# multicharger-redux.net
KiCad netlist of a schematic drawn in EAGLE
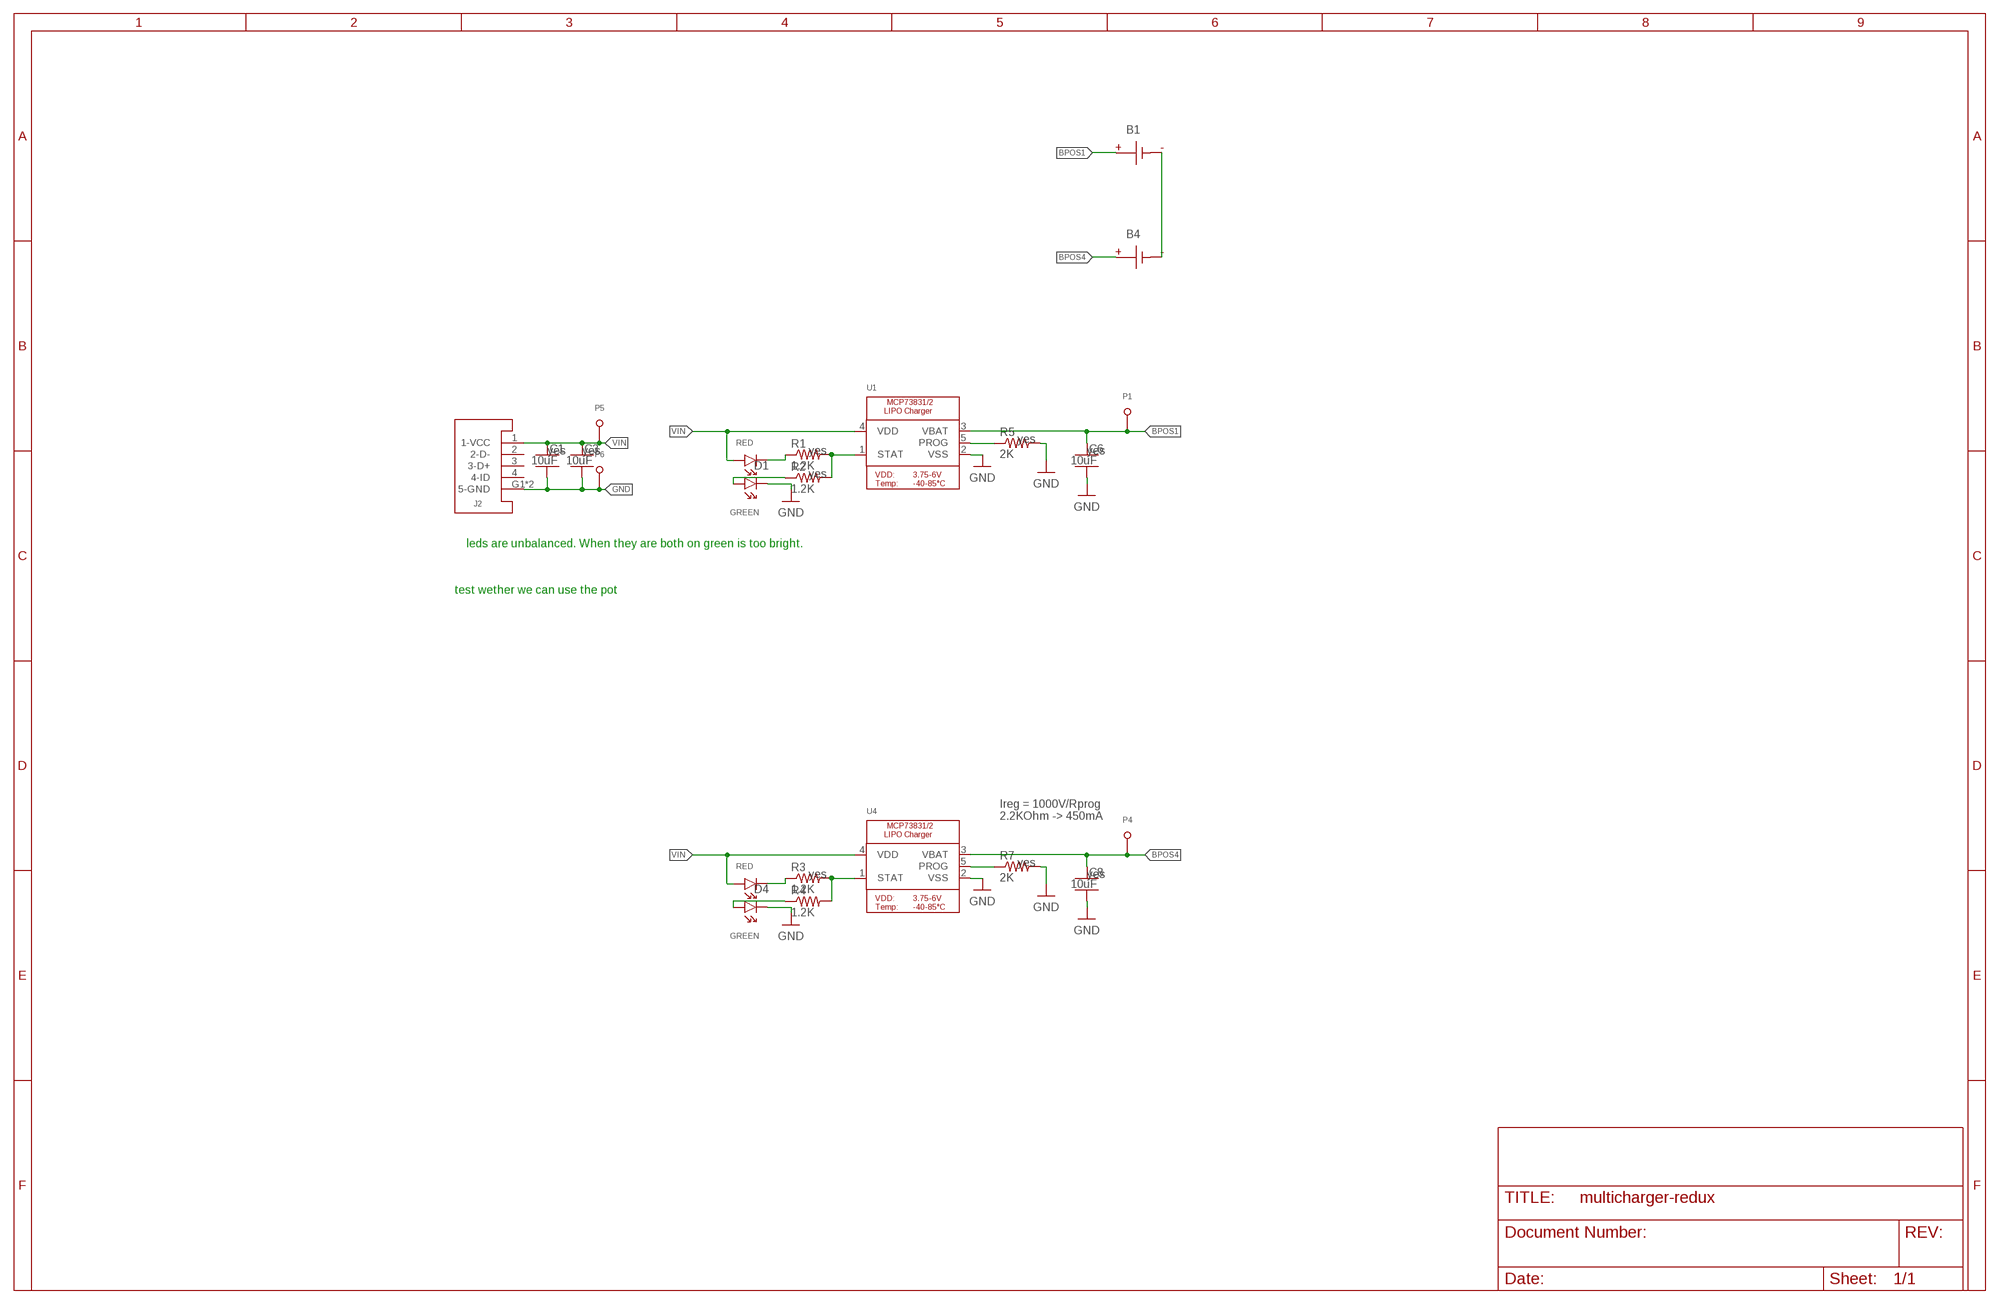
[diagram p0: schematic, sheet 1]

(export (version "E")
  (design (tool "Eeschema 10.0.6"))
  (components
    (comp (ref "B1")
      (value "BATTERY-SMD")
      (footprint "eagle-import:MOLEX-BATTERY-CONNECTOR-SMD-51005-2P")
      (fields (field (name "MFR") "UNKNOWN") (field (name "CREATOR") "Swanson"))
      (libsource (lib "eagle-import") (part "BATTERY-SMD"))
    )
    (comp (ref "B4")
      (value "BATTERY-SMD")
      (footprint "eagle-import:MOLEX-BATTERY-CONNECTOR-SMD-51005-2P")
      (fields (field (name "MFR") "UNKNOWN") (field (name "CREATOR") "Swanson"))
      (libsource (lib "eagle-import") (part "BATTERY-SMD"))
    )
    (comp (ref "C1")
      (value "10uF")
      (footprint "eagle-import:CAPC2012X140_HS")
      (fields
        (field (name "MFR") "TDK")
        (field (name "MPN") "C2012X5R1E106K125AB")
        (field (name "SUBSTITUTE_OK") "yes")
        (field (name "CREATOR") "Swanson")
        (field (name "REVIEWER") "Swanson")
      )
      (libsource (lib "eagle-import") (part "CAPACITOR-NP_SMD-2012-0805_CERAMIC-10UF"))
    )
    (comp (ref "C3")
      (value "10uF")
      (footprint "eagle-import:CAPC2012X140_HS")
      (fields
        (field (name "MFR") "TDK")
        (field (name "MPN") "C2012X5R1E106K125AB")
        (field (name "SUBSTITUTE_OK") "yes")
        (field (name "CREATOR") "Swanson")
        (field (name "REVIEWER") "Swanson")
      )
      (libsource (lib "eagle-import") (part "CAPACITOR-NP_SMD-2012-0805_CERAMIC-10UF"))
    )
    (comp (ref "C6")
      (value "10uF")
      (footprint "eagle-import:CAPC2012X140_HS")
      (fields
        (field (name "MFR") "TDK")
        (field (name "MPN") "C2012X5R1E106K125AB")
        (field (name "SUBSTITUTE_OK") "yes")
        (field (name "CREATOR") "Swanson")
        (field (name "REVIEWER") "Swanson")
      )
      (libsource (lib "eagle-import") (part "CAPACITOR-NP_SMD-2012-0805_CERAMIC-10UF"))
    )
    (comp (ref "C8")
      (value "10uF")
      (footprint "eagle-import:CAPC2012X140_HS")
      (fields
        (field (name "MFR") "TDK")
        (field (name "MPN") "C2012X5R1E106K125AB")
        (field (name "SUBSTITUTE_OK") "yes")
        (field (name "CREATOR") "Swanson")
        (field (name "REVIEWER") "Swanson")
      )
      (libsource (lib "eagle-import") (part "CAPACITOR-NP_SMD-2012-0805_CERAMIC-10UF"))
    )
    (comp (ref "D1")
      (value "LED-2X-GREEN/RED-1.6X1.5MM")
      (footprint "eagle-import:LED-2X-LITE-ON-1.6MMX1.5MM")
      (fields
        (field (name "COLOR2") "GREEN")
        (field (name "COLOR1") "RED")
        (field (name "MFR") "Lite-On Inc.")
        (field (name "MPN") "LTST-C195TGKRKT")
        (field (name "CREATOR") "Swanson")
      )
      (libsource (lib "eagle-import") (part "LED-2X-GREEN/RED-1.6X1.5MM"))
    )
    (comp (ref "D4")
      (value "LED-2X-GREEN/RED-1.6X1.5MM")
      (footprint "eagle-import:LED-2X-LITE-ON-1.6MMX1.5MM")
      (fields
        (field (name "COLOR2") "GREEN")
        (field (name "COLOR1") "RED")
        (field (name "MFR") "Lite-On Inc.")
        (field (name "MPN") "LTST-C195TGKRKT")
        (field (name "CREATOR") "Swanson")
      )
      (libsource (lib "eagle-import") (part "LED-2X-GREEN/RED-1.6X1.5MM"))
    )
    (comp (ref "J2")
      (value "USB-A-SMD-KEYSTONE-931")
      (footprint "eagle-import:USB-A-KEYSTONE-931")
      (fields
        (field (name "MFR") "Keystone Electronics")
        (field (name "MPN") "931")
        (field (name "CREATOR") "Swanson")
      )
      (libsource (lib "eagle-import") (part "USB-A-SMD-KEYSTONE-931"))
    )
    (comp (ref "P1")
      (value "TEST-POINT-1MM")
      (footprint "eagle-import:TEST-POINT-1MM-VIA")
      (fields (field (name "CREATOR") "Swanson"))
      (libsource (lib "eagle-import") (part "TEST-POINT-1MM"))
    )
    (comp (ref "P4")
      (value "TEST-POINT-1MM")
      (footprint "eagle-import:TEST-POINT-1MM-VIA")
      (fields (field (name "CREATOR") "Swanson"))
      (libsource (lib "eagle-import") (part "TEST-POINT-1MM"))
    )
    (comp (ref "P5")
      (value "TEST-POINT-1MM")
      (footprint "eagle-import:TEST-POINT-1MM-VIA")
      (fields (field (name "CREATOR") "Swanson"))
      (libsource (lib "eagle-import") (part "TEST-POINT-1MM"))
    )
    (comp (ref "P6")
      (value "TEST-POINT-1MM")
      (footprint "eagle-import:TEST-POINT-1MM-VIA")
      (fields (field (name "CREATOR") "Swanson"))
      (libsource (lib "eagle-import") (part "TEST-POINT-1MM"))
    )
    (comp (ref "R1")
      (value "1.2K")
      (footprint "eagle-import:RESC2012X60_HS")
      (fields
        (field (name "MFR") "Yageo")
        (field (name "MPN") "RC0805FR-071K2L")
        (field (name "SUBSTITUTE_OK") "yes")
        (field (name "CREATOR") "Swanson")
      )
      (libsource (lib "eagle-import") (part "RESISTOR_SMD-2012-0805-1.2K"))
    )
    (comp (ref "R2")
      (value "1.2K")
      (footprint "eagle-import:RESC2012X60_HS")
      (fields
        (field (name "MFR") "Yageo")
        (field (name "MPN") "RC0805FR-071K2L")
        (field (name "SUBSTITUTE_OK") "yes")
        (field (name "CREATOR") "Swanson")
      )
      (libsource (lib "eagle-import") (part "RESISTOR_SMD-2012-0805-1.2K"))
    )
    (comp (ref "R3")
      (value "1.2K")
      (footprint "eagle-import:RESC2012X60_HS")
      (fields
        (field (name "MFR") "Yageo")
        (field (name "MPN") "RC0805FR-071K2L")
        (field (name "SUBSTITUTE_OK") "yes")
        (field (name "CREATOR") "Swanson")
      )
      (libsource (lib "eagle-import") (part "RESISTOR_SMD-2012-0805-1.2K"))
    )
    (comp (ref "R4")
      (value "1.2K")
      (footprint "eagle-import:RESC2012X60_HS")
      (fields
        (field (name "MFR") "Yageo")
        (field (name "MPN") "RC0805FR-071K2L")
        (field (name "CREATOR") "Swanson")
      )
      (libsource (lib "eagle-import") (part "RESISTOR_SMD-2012-0805-1.2K"))
    )
    (comp (ref "R5")
      (value "2K")
      (footprint "eagle-import:RESC2012X60_HS")
      (fields
        (field (name "MFR") "YAGEO")
        (field (name "MPN") "AC0805FR-071K2L")
        (field (name "SUBSTITUTE_OK") "yes")
        (field (name "CREATOR") "Swanson")
      )
      (libsource (lib "eagle-import") (part "RESISTOR_SMD-2012-0805-2K"))
    )
    (comp (ref "R7")
      (value "2K")
      (footprint "eagle-import:RESC2012X60_HS")
      (fields
        (field (name "MFR") "YAGEO")
        (field (name "MPN") "AC0805FR-071K2L")
        (field (name "SUBSTITUTE_OK") "yes")
        (field (name "CREATOR") "Swanson")
      )
      (libsource (lib "eagle-import") (part "RESISTOR_SMD-2012-0805-2K"))
    )
    (comp (ref "U1")
      (value "MCP73831T-2ACI/OT")
      (footprint "eagle-import:SOT23-5")
      (fields (field (name "MFR") "Microchip Technology") (field (name "CREATOR") "Adafruit"))
      (libsource (lib "eagle-import") (part "MCP73831/2"))
    )
    (comp (ref "U4")
      (value "MCP73831T-2ACI/OT")
      (footprint "eagle-import:SOT23-5")
      (fields (field (name "MFR") "Microchip Technology") (field (name "CREATOR") "Adafruit"))
      (libsource (lib "eagle-import") (part "MCP73831/2"))
    )
  )
  (nets
    (net (code "1") (name "BPOS1") (class "Default")
      (node (ref "B1") (pin "P") (pinfunction "P_P") (pintype "bidirectional"))
      (node (ref "C6") (pin "1") (pinfunction "1_1") (pintype "passive"))
      (node (ref "P1") (pin "T") (pinfunction "T_T") (pintype "bidirectional"))
      (node (ref "U1") (pin "3") (pinfunction "VBAT_3") (pintype "power_in"))
    )
    (net (code "2") (name "BPOS4") (class "Default")
      (node (ref "B4") (pin "P") (pinfunction "P_P") (pintype "bidirectional"))
      (node (ref "C8") (pin "1") (pinfunction "1_1") (pintype "passive"))
      (node (ref "P4") (pin "T") (pinfunction "T_T") (pintype "bidirectional"))
      (node (ref "U4") (pin "3") (pinfunction "VBAT_3") (pintype "power_in"))
    )
    (net (code "3") (name "GND") (class "Default")
      (node (ref "B1") (pin "G") (pinfunction "N_G") (pintype "bidirectional"))
      (node (ref "B1") (pin "G2") (pinfunction "N_G2") (pintype "bidirectional"))
      (node (ref "B1") (pin "G3") (pinfunction "N_G3") (pintype "bidirectional"))
      (node (ref "B4") (pin "G") (pinfunction "N_G") (pintype "bidirectional"))
      (node (ref "B4") (pin "G2") (pinfunction "N_G2") (pintype "bidirectional"))
      (node (ref "B4") (pin "G3") (pinfunction "N_G3") (pintype "bidirectional"))
      (node (ref "C1") (pin "2") (pinfunction "2_2") (pintype "passive"))
      (node (ref "C3") (pin "2") (pinfunction "2_2") (pintype "passive"))
      (node (ref "C6") (pin "2") (pinfunction "2_2") (pintype "passive"))
      (node (ref "C8") (pin "2") (pinfunction "2_2") (pintype "passive"))
      (node (ref "D1") (pin "C1") (pinfunction "C1_C1") (pintype "passive"))
      (node (ref "D4") (pin "C1") (pinfunction "C1_C1") (pintype "passive"))
      (node (ref "J2") (pin "G1") (pinfunction "5-GND_G1") (pintype "bidirectional"))
      (node (ref "J2") (pin "G2") (pinfunction "5-GND_G2") (pintype "bidirectional"))
      (node (ref "P6") (pin "T") (pinfunction "T_T") (pintype "bidirectional"))
      (node (ref "R5") (pin "2") (pinfunction "2_2") (pintype "passive"))
      (node (ref "R7") (pin "2") (pinfunction "2_2") (pintype "passive"))
      (node (ref "U1") (pin "2") (pinfunction "VSS_2") (pintype "power_in"))
      (node (ref "U4") (pin "2") (pinfunction "VSS_2") (pintype "power_in"))
    )
    (net (code "4") (name "Net-(D1-PadA1)") (class "Default")
      (node (ref "D1") (pin "A1") (pinfunction "A1_A1") (pintype "passive"))
      (node (ref "R2") (pin "1") (pinfunction "1_1") (pintype "passive"))
    )
    (net (code "5") (name "Net-(D1-PadC2)") (class "Default")
      (node (ref "D1") (pin "C2") (pinfunction "C2_C2") (pintype "passive"))
      (node (ref "R1") (pin "1") (pinfunction "1_1") (pintype "passive"))
    )
    (net (code "6") (name "Net-(D4-PadA1)") (class "Default")
      (node (ref "D4") (pin "A1") (pinfunction "A1_A1") (pintype "passive"))
      (node (ref "R4") (pin "1") (pinfunction "1_1") (pintype "passive"))
    )
    (net (code "7") (name "Net-(D4-PadC2)") (class "Default")
      (node (ref "D4") (pin "C2") (pinfunction "C2_C2") (pintype "passive"))
      (node (ref "R3") (pin "1") (pinfunction "1_1") (pintype "passive"))
    )
    (net (code "8") (name "Net-(U1-PROG)") (class "Default")
      (node (ref "R5") (pin "1") (pinfunction "1_1") (pintype "passive"))
      (node (ref "U1") (pin "5") (pinfunction "PROG_5") (pintype "input"))
    )
    (net (code "9") (name "Net-(U1-STAT)") (class "Default")
      (node (ref "R1") (pin "2") (pinfunction "2_2") (pintype "passive"))
      (node (ref "R2") (pin "2") (pinfunction "2_2") (pintype "passive"))
      (node (ref "U1") (pin "1") (pinfunction "STAT_1") (pintype "output"))
    )
    (net (code "10") (name "Net-(U4-PROG)") (class "Default")
      (node (ref "R7") (pin "1") (pinfunction "1_1") (pintype "passive"))
      (node (ref "U4") (pin "5") (pinfunction "PROG_5") (pintype "input"))
    )
    (net (code "11") (name "Net-(U4-STAT)") (class "Default")
      (node (ref "R3") (pin "2") (pinfunction "2_2") (pintype "passive"))
      (node (ref "R4") (pin "2") (pinfunction "2_2") (pintype "passive"))
      (node (ref "U4") (pin "1") (pinfunction "STAT_1") (pintype "output"))
    )
    (net (code "12") (name "VIN") (class "Default")
      (node (ref "C1") (pin "1") (pinfunction "1_1") (pintype "passive"))
      (node (ref "C3") (pin "1") (pinfunction "1_1") (pintype "passive"))
      (node (ref "D1") (pin "A2") (pinfunction "A2_A2") (pintype "passive"))
      (node (ref "D4") (pin "A2") (pinfunction "A2_A2") (pintype "passive"))
      (node (ref "J2") (pin "1") (pinfunction "1-VCC_1") (pintype "bidirectional"))
      (node (ref "P5") (pin "T") (pinfunction "T_T") (pintype "bidirectional"))
      (node (ref "U1") (pin "4") (pinfunction "VDD_4") (pintype "power_in"))
      (node (ref "U4") (pin "4") (pinfunction "VDD_4") (pintype "power_in"))
    )
    (net (code "13") (name "unconnected-(J2-2-D--Pad2)") (class "Default")
      (node (ref "J2") (pin "2") (pinfunction "2-D-_2") (pintype "bidirectional"))
    )
    (net (code "14") (name "unconnected-(J2-3-D+-Pad3)") (class "Default")
      (node (ref "J2") (pin "3") (pinfunction "3-D+_3") (pintype "bidirectional"))
    )
    (net (code "15") (name "unconnected-(J2-4-ID-Pad4)") (class "Default")
      (node (ref "J2") (pin "4") (pinfunction "4-ID_4") (pintype "bidirectional"))
    )
  )
)
